# pa-5g.net
KiCad netlist of a schematic drawn in Altium Designer
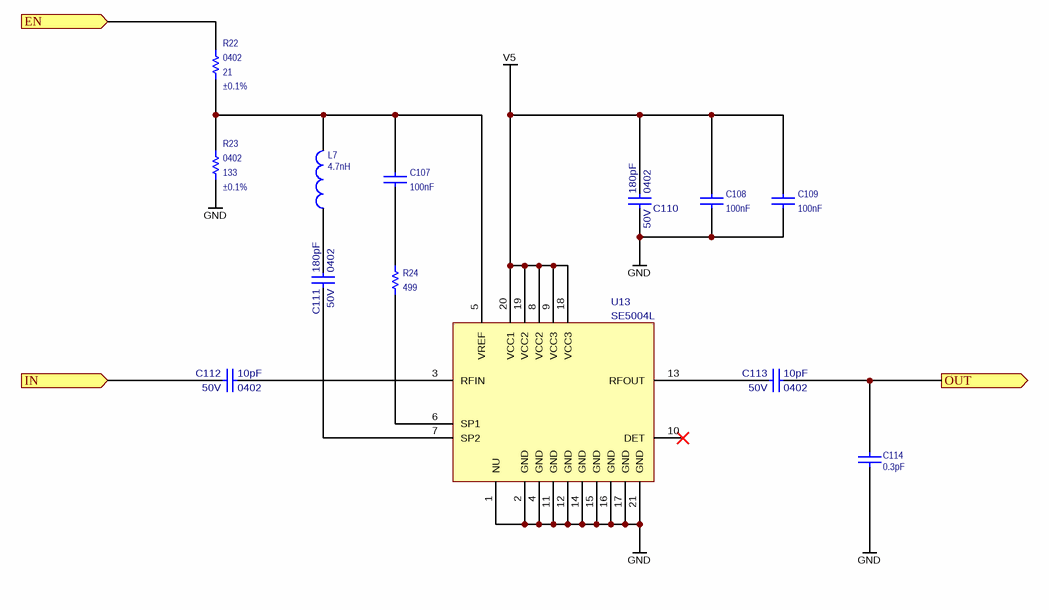
[diagram p0: pa-5g.SchDoc]

(export (version "E")
  (design (tool "Eeschema 10.0.6"))
  (components
    (comp (ref "C107")
      (value "100nF")
      (footprint "CAPC100X50X55L25N")
      (description "Ceramic Capacitor 100nF ±10% 16V X7R 0402")
      (fields (field (name "VOLTAGE") "16V") (field (name "MANUFACTURER") "Murata"))
      (libsource (lib "Graviton") (part "CAP 0402"))
    )
    (comp (ref "C108")
      (value "100nF")
      (footprint "CAPC100X50X55L25N")
      (description "Ceramic Capacitor 100nF ±10% 16V X7R 0402")
      (fields (field (name "VOLTAGE") "16V") (field (name "MANUFACTURER") "Murata"))
      (libsource (lib "Graviton") (part "CAP 0402"))
    )
    (comp (ref "C109")
      (value "100nF")
      (footprint "CAPC100X50X55L25N")
      (description "Ceramic Capacitor 100nF ±10% 16V X7R 0402")
      (fields (field (name "VOLTAGE") "16V") (field (name "MANUFACTURER") "Murata"))
      (libsource (lib "Graviton") (part "CAP 0402"))
    )
    (comp (ref "C110")
      (value "180pF")
      (footprint "CAPC160X80X90L20N")
      (description "Ceramic Capacitor 180pF ±5% 50V C0G 0402")
      (fields
        (field (name "MANUFACTURER") "Vishay")
        (field (name "TOLERANCE") "±5%")
        (field (name "PACKAGE") "0402")
        (field (name "VOLTAGE") "50V")
      )
      (libsource (lib "capacitors") (part "CAP"))
    )
    (comp (ref "C111")
      (value "180pF")
      (footprint "CAPC160X80X90L20N")
      (description "Ceramic Capacitor 180pF ±5% 50V C0G 0402")
      (fields
        (field (name "MANUFACTURER") "Vishay")
        (field (name "TOLERANCE") "±5%")
        (field (name "PACKAGE") "0402")
        (field (name "VOLTAGE") "50V")
      )
      (libsource (lib "capacitors") (part "CAP"))
    )
    (comp (ref "C112")
      (value "10pF")
      (footprint "CAPC160X80X90L20N")
      (description "Ceramic Capacitor 10pF ±5% 50V C0G 0402")
      (fields
        (field (name "MANUFACTURER") "Vishay")
        (field (name "TOLERANCE") "±5%")
        (field (name "PACKAGE") "0402")
        (field (name "VOLTAGE") "50V")
      )
      (libsource (lib "capacitors") (part "CAP"))
    )
    (comp (ref "C113")
      (value "10pF")
      (footprint "CAPC160X80X90L20N")
      (description "Ceramic Capacitor 10pF ±5% 50V C0G 0402")
      (fields
        (field (name "MANUFACTURER") "Vishay")
        (field (name "TOLERANCE") "±5%")
        (field (name "PACKAGE") "0402")
        (field (name "VOLTAGE") "50V")
      )
      (libsource (lib "capacitors") (part "CAP"))
    )
    (comp (ref "C114")
      (value "0.3pF")
      (footprint "generic:0402")
      (description "Ceramic Capacitor 20pF ±1% 50V NP0 0402")
      (fields (field (name "VOLTAGE") "50V") (field (name "MANUFACTURER") "Kemet"))
      (libsource (lib "PopRock") (part "CAP 0402"))
    )
    (comp (ref "L7")
      (value "4.7nH")
      (footprint "0402")
      (description "Inductor Wirewound 4.7nH ±0.2nH 0402")
      (fields (field (name "MANUFACTURER") "Murata") (field (name "TOLERANCE") "±0.2nH"))
      (libsource (lib "generic") (part "INDUCTOR"))
    )
    (comp (ref "R22")
      (value "21")
      (footprint "RESC1005X40N")
      (description "Thin Film Resistor 21 +/-0.1% SMD 0402")
      (fields
        (field (name "TOLERANCE") "±0.1%")
        (field (name "MANUFACTURER") "Panasoinc")
        (field (name "POWER") "0.063W")
        (field (name "PACKAGE") "0402")
      )
      (libsource (lib "generic") (part "RES"))
    )
    (comp (ref "R23")
      (value "133")
      (footprint "RESC1005X40N")
      (description "Thin Film Resistor 133 +/-0.1% SMD 0402")
      (fields
        (field (name "TOLERANCE") "±0.1%")
        (field (name "MANUFACTURER") "Panasoinc")
        (field (name "POWER") "0.063W")
        (field (name "PACKAGE") "0402")
      )
      (libsource (lib "generic") (part "RES"))
    )
    (comp (ref "R24")
      (value "499")
      (footprint "generic:RESC1005X40N")
      (description "Thin Film Resistor 499 Ohm ±0.5% 0402")
      (fields (field (name "MANUFACTURER") "Vishay") (field (name "TOLERANCE") "±0.5%"))
      (libsource (lib "Graviton") (part "RES 0603"))
    )
    (comp (ref "U13")
      (value "SE5004L")
      (footprint "SE5004L")
      (description "5 GHz, 26dBm Power Amplifier")
      (libsource (lib "skyworks") (part "SE5004L"))
    )
  )
  (nets
    (net (code "1") (name "/EN") (class "Default")
      (node (ref "R22") (pin "2") (pinfunction "2_2") (pintype "passive"))
    )
    (net (code "2") (name "/IN") (class "Default")
      (node (ref "C112") (pin "1") (pinfunction "1_1") (pintype "passive"))
    )
    (net (code "3") (name "/OUT") (class "Default")
      (node (ref "C113") (pin "2") (pinfunction "2_2") (pintype "passive"))
      (node (ref "C114") (pin "2") (pinfunction "2_2") (pintype "passive"))
    )
    (net (code "4") (name "GND") (class "Default")
      (node (ref "C108") (pin "1") (pinfunction "1_1") (pintype "passive"))
      (node (ref "C109") (pin "1") (pinfunction "1_1") (pintype "passive"))
      (node (ref "C110") (pin "1") (pinfunction "1_1") (pintype "passive"))
      (node (ref "C114") (pin "1") (pinfunction "1_1") (pintype "passive"))
      (node (ref "R23") (pin "1") (pinfunction "1_1") (pintype "passive"))
      (node (ref "U13") (pin "1") (pinfunction "NU_1") (pintype "passive"))
      (node (ref "U13") (pin "11") (pinfunction "GND_11") (pintype "passive"))
      (node (ref "U13") (pin "12") (pinfunction "GND_12") (pintype "passive"))
      (node (ref "U13") (pin "14") (pinfunction "GND_14") (pintype "passive"))
      (node (ref "U13") (pin "15") (pinfunction "GND_15") (pintype "passive"))
      (node (ref "U13") (pin "16") (pinfunction "GND_16") (pintype "passive"))
      (node (ref "U13") (pin "17") (pinfunction "GND_17") (pintype "passive"))
      (node (ref "U13") (pin "2") (pinfunction "GND_2") (pintype "passive"))
      (node (ref "U13") (pin "21") (pinfunction "GND_21") (pintype "passive"))
      (node (ref "U13") (pin "4") (pinfunction "GND_4") (pintype "passive"))
    )
    (net (code "5") (name "Net-(C107-Pad1)") (class "Default")
      (node (ref "C107") (pin "1") (pinfunction "1_1") (pintype "passive"))
      (node (ref "R24") (pin "2") (pinfunction "2_2") (pintype "passive"))
    )
    (net (code "6") (name "Net-(C111-Pad2)") (class "Default")
      (node (ref "C111") (pin "2") (pinfunction "2_2") (pintype "passive"))
      (node (ref "L7") (pin "1") (pinfunction "1_1") (pintype "passive"))
    )
    (net (code "7") (name "Net-(U13-RFIN)") (class "Default")
      (node (ref "C112") (pin "2") (pinfunction "2_2") (pintype "passive"))
      (node (ref "U13") (pin "3") (pinfunction "RFIN_3") (pintype "passive"))
    )
    (net (code "8") (name "Net-(U13-RFOUT)") (class "Default")
      (node (ref "C113") (pin "1") (pinfunction "1_1") (pintype "passive"))
      (node (ref "U13") (pin "13") (pinfunction "RFOUT_13") (pintype "passive"))
    )
    (net (code "9") (name "Net-(U13-SP1)") (class "Default")
      (node (ref "R24") (pin "1") (pinfunction "1_1") (pintype "passive"))
      (node (ref "U13") (pin "6") (pinfunction "SP1_6") (pintype "passive"))
    )
    (net (code "10") (name "Net-(U13-SP2)") (class "Default")
      (node (ref "C111") (pin "1") (pinfunction "1_1") (pintype "passive"))
      (node (ref "U13") (pin "7") (pinfunction "SP2_7") (pintype "passive"))
    )
    (net (code "11") (name "Net-(U13-VREF)") (class "Default")
      (node (ref "C107") (pin "2") (pinfunction "2_2") (pintype "passive"))
      (node (ref "L7") (pin "2") (pinfunction "2_2") (pintype "passive"))
      (node (ref "R22") (pin "1") (pinfunction "1_1") (pintype "passive"))
      (node (ref "R23") (pin "2") (pinfunction "2_2") (pintype "passive"))
      (node (ref "U13") (pin "5") (pinfunction "VREF_5") (pintype "passive"))
    )
    (net (code "12") (name "V5") (class "Default")
      (node (ref "C108") (pin "2") (pinfunction "2_2") (pintype "passive"))
      (node (ref "C109") (pin "2") (pinfunction "2_2") (pintype "passive"))
      (node (ref "C110") (pin "2") (pinfunction "2_2") (pintype "passive"))
      (node (ref "U13") (pin "18") (pinfunction "VCC3_18") (pintype "passive"))
      (node (ref "U13") (pin "19") (pinfunction "VCC2_19") (pintype "passive"))
      (node (ref "U13") (pin "20") (pinfunction "VCC1_20") (pintype "passive"))
      (node (ref "U13") (pin "8") (pinfunction "VCC2_8") (pintype "passive"))
      (node (ref "U13") (pin "9") (pinfunction "VCC3_9") (pintype "passive"))
    )
    (net (code "13") (name "unconnected-(U13-DET-Pad10)") (class "Default")
      (node (ref "U13") (pin "10") (pinfunction "DET_10") (pintype "passive+no_connect"))
    )
  )
)
